# RTI-Dome-eth-ENC.net
KiCad netlist of a schematic drawn in EAGLE
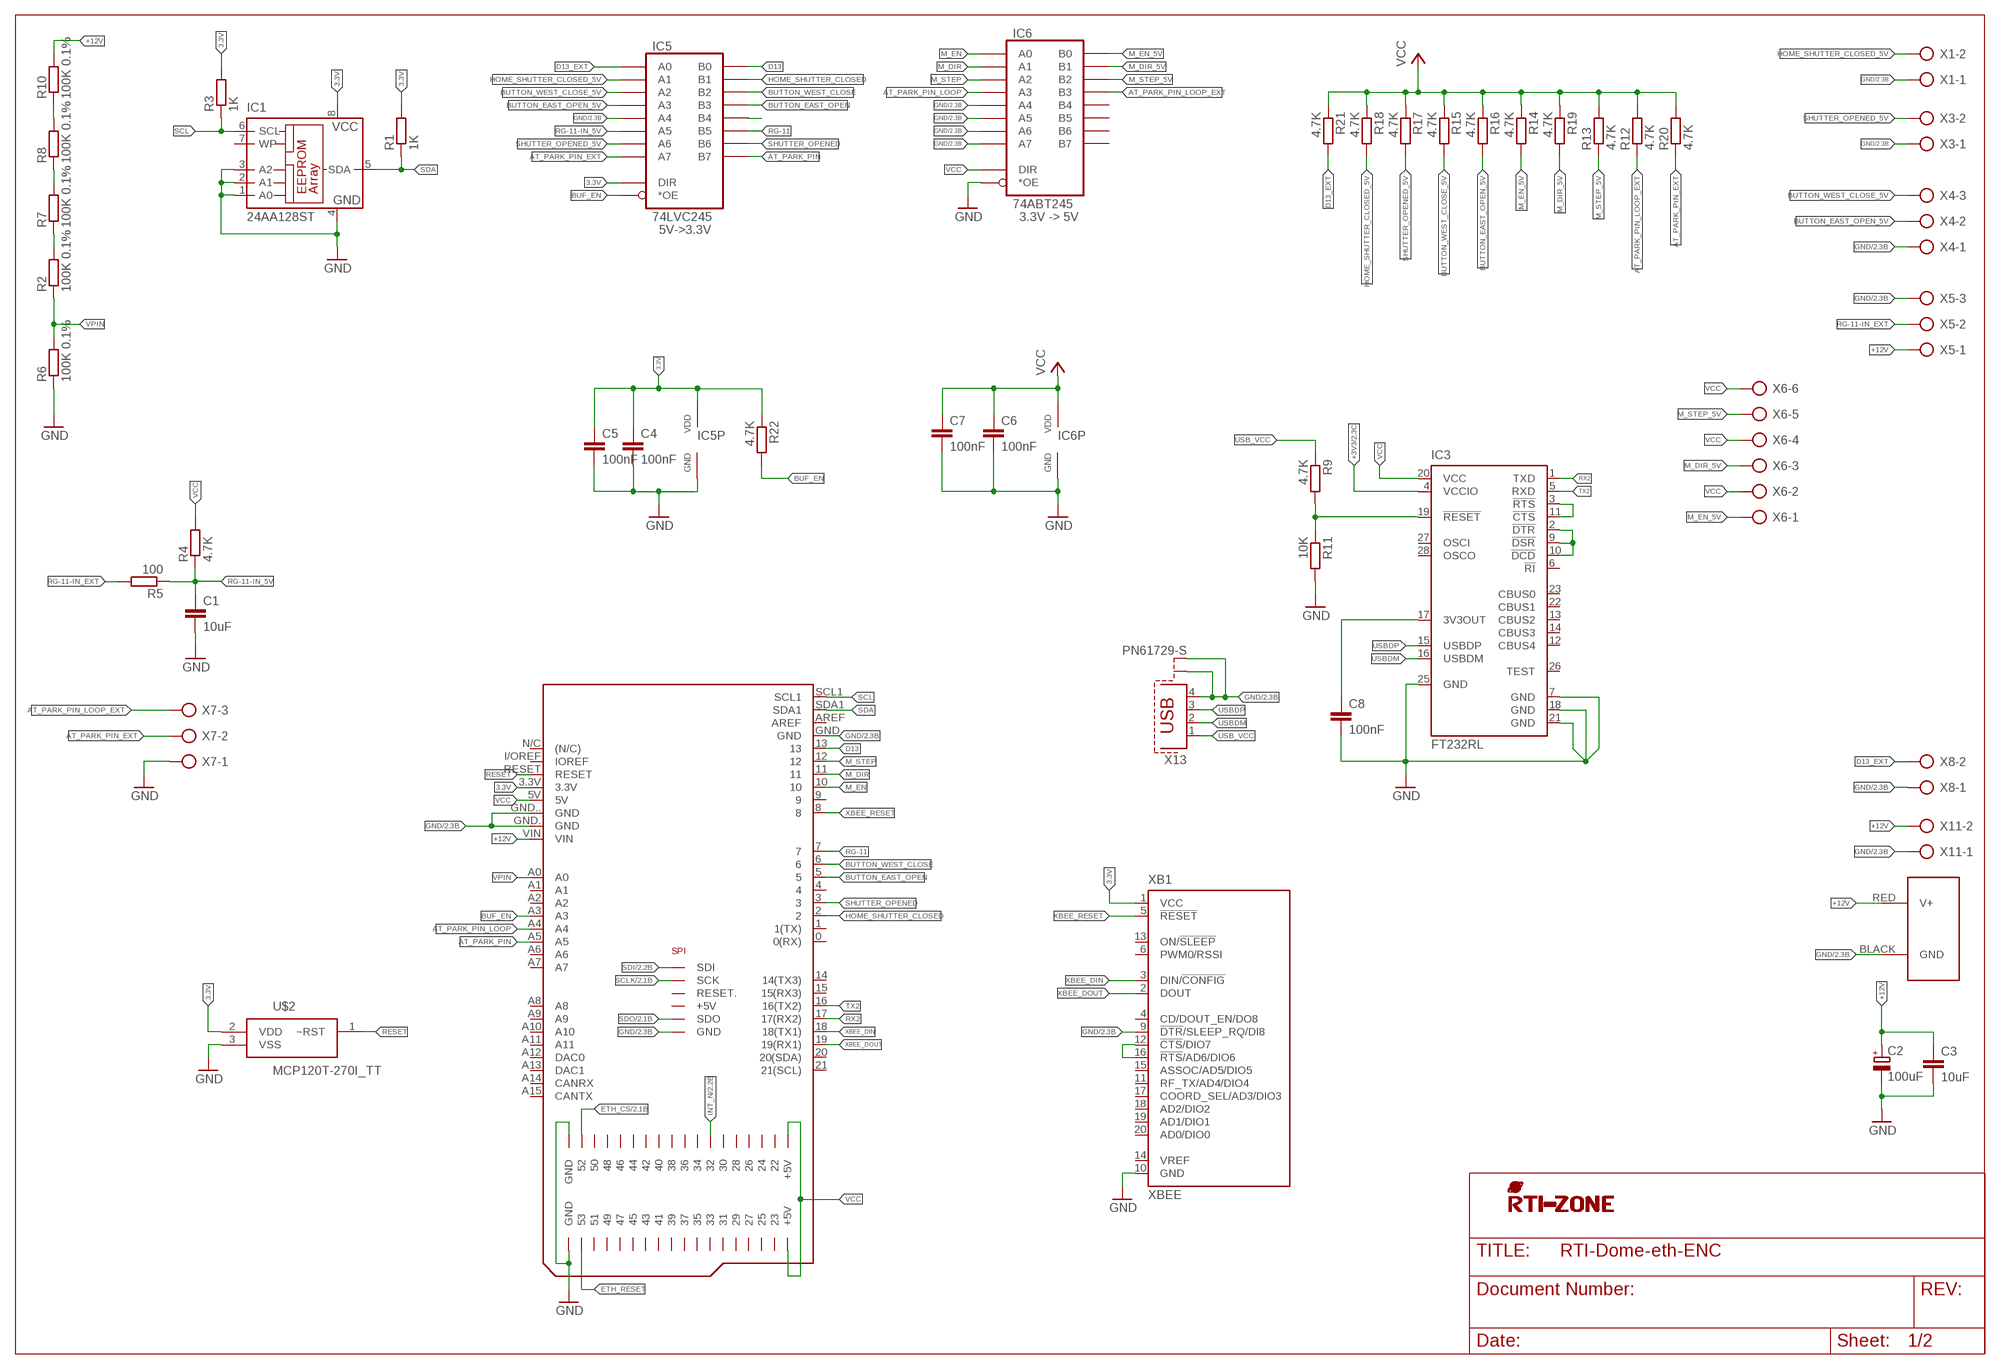
[diagram p0: schematic, sheet 1]
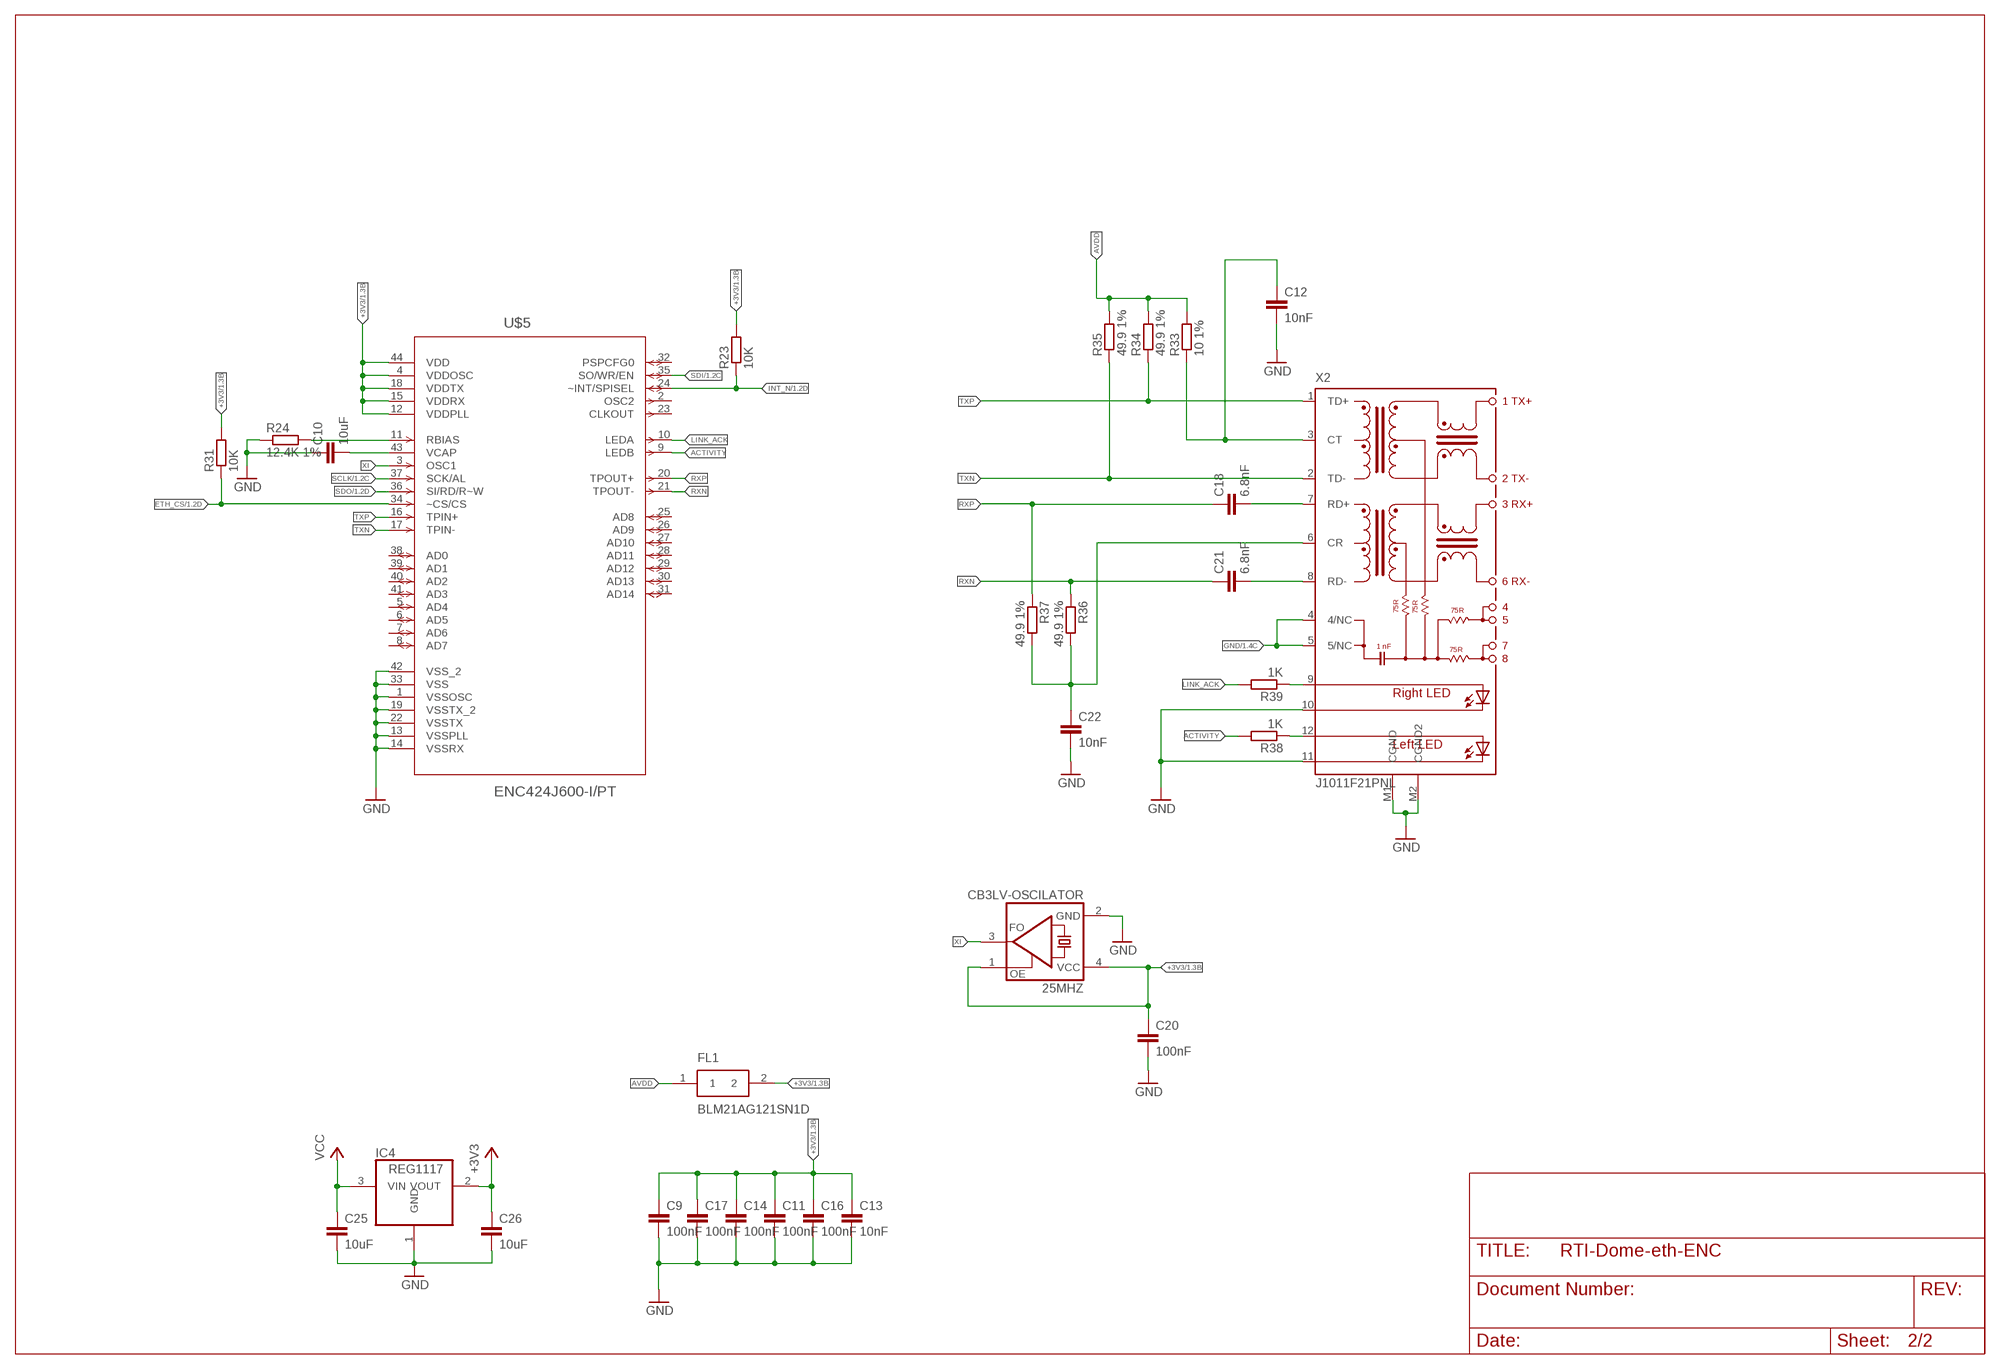
[diagram p1: schematic, sheet 2]

(export (version "E")
  (design (tool "Eeschema 10.0.6"))
  (components
    (comp (ref "25MHZ")
      (value "CB3LV-OSCILATOR")
      (footprint "eagle-import:SMD-7050_4P")
      (fields (field (name "MPN") "O705025MEDH4MI"))
      (libsource (lib "eagle-import") (part "CB3LV-OSCILATOR"))
    )
    (comp (ref "C9")
      (value "100nF")
      (footprint "eagle-import:C0805")
      (libsource (lib "eagle-import") (part "C-EU'0805'"))
    )
    (comp (ref "C10")
      (value "10uF")
      (footprint "eagle-import:C0805")
      (libsource (lib "eagle-import") (part "C-EU'0805'"))
    )
    (comp (ref "C11")
      (value "100nF")
      (footprint "eagle-import:C0805")
      (libsource (lib "eagle-import") (part "C-EU'0805'"))
    )
    (comp (ref "C12")
      (value "10nF")
      (footprint "eagle-import:C0805")
      (libsource (lib "eagle-import") (part "C-EU'0805'"))
    )
    (comp (ref "C13")
      (value "10nF")
      (footprint "eagle-import:C0805")
      (libsource (lib "eagle-import") (part "C-EU'0805'"))
    )
    (comp (ref "C14")
      (value "100nF")
      (footprint "eagle-import:C0805")
      (libsource (lib "eagle-import") (part "C-EU'0805'"))
    )
    (comp (ref "C16")
      (value "100nF")
      (footprint "eagle-import:C0805")
      (libsource (lib "eagle-import") (part "C-EU'0805'"))
    )
    (comp (ref "C17")
      (value "100nF")
      (footprint "eagle-import:C0805")
      (libsource (lib "eagle-import") (part "C-EU'0805'"))
    )
    (comp (ref "C18")
      (value "6.8nF")
      (footprint "eagle-import:C0805")
      (libsource (lib "eagle-import") (part "C-EU'0805'"))
    )
    (comp (ref "C20")
      (value "100nF")
      (footprint "eagle-import:C0805")
      (libsource (lib "eagle-import") (part "C-EU'0805'"))
    )
    (comp (ref "C21")
      (value "6.8nF")
      (footprint "eagle-import:C0805")
      (libsource (lib "eagle-import") (part "C-EU'0805'"))
    )
    (comp (ref "C22")
      (value "10nF")
      (footprint "eagle-import:C0805")
      (libsource (lib "eagle-import") (part "C-EU'0805'"))
    )
    (comp (ref "C25")
      (value "10uF")
      (footprint "eagle-import:C1206")
      (libsource (lib "eagle-import") (part "C-EU'1206'"))
    )
    (comp (ref "C26")
      (value "10uF")
      (footprint "eagle-import:C1206")
      (libsource (lib "eagle-import") (part "C-EU'1206'"))
    )
    (comp (ref "FL1")
      (value "BLM21AG121SN1D")
      (footprint "eagle-import:L0805")
      (libsource (lib "eagle-import") (part "BLM21AG121SN1D"))
    )
    (comp (ref "IC4")
      (value "REG1117")
      (footprint "eagle-import:SOT223")
      (fields (field (name "MPN") "REG1117-3.3/2K5"))
      (libsource (lib "eagle-import") (part "REG1117"))
    )
    (comp (ref "R23")
      (value "10K")
      (footprint "eagle-import:R0805")
      (libsource (lib "eagle-import") (part "R-EU'0805'"))
    )
    (comp (ref "R24")
      (value "12.4K 1%")
      (footprint "eagle-import:R0805")
      (libsource (lib "eagle-import") (part "R-EU'0805'"))
    )
    (comp (ref "R31")
      (value "10K")
      (footprint "eagle-import:R0805")
      (libsource (lib "eagle-import") (part "R-EU'0805'"))
    )
    (comp (ref "R33")
      (value "10 1%")
      (footprint "eagle-import:R0805")
      (libsource (lib "eagle-import") (part "R-EU'0805'"))
    )
    (comp (ref "R34")
      (value "49.9 1%")
      (footprint "eagle-import:R0805")
      (libsource (lib "eagle-import") (part "R-EU'0805'"))
    )
    (comp (ref "R35")
      (value "49.9 1%")
      (footprint "eagle-import:R0805")
      (libsource (lib "eagle-import") (part "R-EU'0805'"))
    )
    (comp (ref "R36")
      (value "49.9 1%")
      (footprint "eagle-import:R0805")
      (libsource (lib "eagle-import") (part "R-EU'0805'"))
    )
    (comp (ref "R37")
      (value "49.9 1%")
      (footprint "eagle-import:R0805")
      (libsource (lib "eagle-import") (part "R-EU'0805'"))
    )
    (comp (ref "R38")
      (value "1K")
      (footprint "eagle-import:R0805")
      (libsource (lib "eagle-import") (part "R-EU'0805'"))
    )
    (comp (ref "R39")
      (value "1K")
      (footprint "eagle-import:R0805")
      (libsource (lib "eagle-import") (part "R-EU'0805'"))
    )
    (comp (ref "U$5")
      (value "ENC424J600-I/PT")
      (footprint "eagle-import:QFP50P1200X1200X120-44N")
      (fields (field (name "MPN") "enc424j600-I/pt") (field (name "MPN_1") "ENC424J600-I/PT"))
      (libsource (lib "eagle-import") (part "ENC424J600-I/PT"))
    )
    (comp (ref "X2")
      (value "J1011F21PNL")
      (footprint "eagle-import:J1")
      (libsource (lib "eagle-import") (part "J1011F21PNL"))
    )
    (comp (ref "C1")
      (value "10uF")
      (footprint "eagle-import:C0805")
      (libsource (lib "eagle-import") (part "C-EU'0805'"))
    )
    (comp (ref "C2")
      (value "100uF")
      (footprint "eagle-import:UD-10X10_NICHICON")
      (libsource (lib "eagle-import") (part "CPOL-EU"))
    )
    (comp (ref "C3")
      (value "10uF")
      (footprint "eagle-import:C0805")
      (libsource (lib "eagle-import") (part "C-EU'0805'"))
    )
    (comp (ref "C4")
      (value "100nF")
      (footprint "eagle-import:C0805")
      (libsource (lib "eagle-import") (part "C-EU'0805'"))
    )
    (comp (ref "C5")
      (value "100nF")
      (footprint "eagle-import:C0805")
      (libsource (lib "eagle-import") (part "C-EU'0805'"))
    )
    (comp (ref "C6")
      (value "100nF")
      (footprint "eagle-import:C0805")
      (libsource (lib "eagle-import") (part "C-EU'0805'"))
    )
    (comp (ref "C7")
      (value "100nF")
      (footprint "eagle-import:C0805")
      (libsource (lib "eagle-import") (part "C-EU'0805'"))
    )
    (comp (ref "C8")
      (value "100nF")
      (footprint "eagle-import:C0805")
      (libsource (lib "eagle-import") (part "C-EU'0805'"))
    )
    (comp (ref "IC1")
      (value "24AA128ST")
      (footprint "eagle-import:TSSOP8")
      (fields (field (name "MF") "MICROCHIP") (field (name "MPN") "24AA128-I/ST"))
      (libsource (lib "eagle-import") (part "24STAA128"))
    )
    (comp (ref "IC3")
      (value "FT232RL")
      (footprint "eagle-import:SSOP28")
      (libsource (lib "eagle-import") (part "FT232RL"))
    )
    (comp (ref "IC5")
      (value "74LVC245")
      (footprint "eagle-import:TSSOP20")
      (fields (field (name "MPN") "74LVC245APW,118"))
      (libsource (lib "eagle-import") (part "74245LVC"))
    )
    (comp (ref "IC6")
      (value "74ABT245")
      (footprint "eagle-import:TSSOP20")
      (fields (field (name "MPN") "SN74ABT245BDWR"))
      (libsource (lib "eagle-import") (part "74245ABT"))
    )
    (comp (ref "J1")
      (value "POWERPOLE_POWER45A")
      (footprint "eagle-import:POWERPOLE_PAIR_45A")
      (libsource (lib "eagle-import") (part "POWERPOLE_POWER45A"))
    )
    (comp (ref "R1")
      (value "1K")
      (footprint "eagle-import:R0805")
      (libsource (lib "eagle-import") (part "R-EU'0805'"))
    )
    (comp (ref "R2")
      (value "100K 0.1%")
      (footprint "eagle-import:R0805")
      (libsource (lib "eagle-import") (part "R-EU'0805'"))
    )
    (comp (ref "R3")
      (value "1K")
      (footprint "eagle-import:R0805")
      (libsource (lib "eagle-import") (part "R-EU'0805'"))
    )
    (comp (ref "R4")
      (value "4.7K")
      (footprint "eagle-import:R0805")
      (libsource (lib "eagle-import") (part "R-EU'0805'"))
    )
    (comp (ref "R5")
      (value "100")
      (footprint "eagle-import:R0805")
      (libsource (lib "eagle-import") (part "R-EU'0805'"))
    )
    (comp (ref "R6")
      (value "100K 0.1%")
      (footprint "eagle-import:R0805")
      (libsource (lib "eagle-import") (part "R-EU'0805'"))
    )
    (comp (ref "R7")
      (value "100K 0.1%")
      (footprint "eagle-import:R0805")
      (libsource (lib "eagle-import") (part "R-EU'0805'"))
    )
    (comp (ref "R8")
      (value "100K 0.1%")
      (footprint "eagle-import:R0805")
      (libsource (lib "eagle-import") (part "R-EU'0805'"))
    )
    (comp (ref "R9")
      (value "4.7K")
      (footprint "eagle-import:R0805")
      (libsource (lib "eagle-import") (part "R-EU'0805'"))
    )
    (comp (ref "R10")
      (value "100K 0.1%")
      (footprint "eagle-import:R0805")
      (libsource (lib "eagle-import") (part "R-EU'0805'"))
    )
    (comp (ref "R11")
      (value "10K")
      (footprint "eagle-import:R0805")
      (libsource (lib "eagle-import") (part "R-EU'0805'"))
    )
    (comp (ref "R12")
      (value "4.7K")
      (footprint "eagle-import:R0805")
      (libsource (lib "eagle-import") (part "R-EU'0805'"))
    )
    (comp (ref "R13")
      (value "4.7K")
      (footprint "eagle-import:R0805")
      (libsource (lib "eagle-import") (part "R-EU'0805'"))
    )
    (comp (ref "R14")
      (value "4.7K")
      (footprint "eagle-import:R0805")
      (libsource (lib "eagle-import") (part "R-EU'0805'"))
    )
    (comp (ref "R15")
      (value "4.7K")
      (footprint "eagle-import:R0805")
      (libsource (lib "eagle-import") (part "R-EU'0805'"))
    )
    (comp (ref "R16")
      (value "4.7K")
      (footprint "eagle-import:R0805")
      (libsource (lib "eagle-import") (part "R-EU'0805'"))
    )
    (comp (ref "R17")
      (value "4.7K")
      (footprint "eagle-import:R0805")
      (libsource (lib "eagle-import") (part "R-EU'0805'"))
    )
    (comp (ref "R18")
      (value "4.7K")
      (footprint "eagle-import:R0805")
      (libsource (lib "eagle-import") (part "R-EU'0805'"))
    )
    (comp (ref "R19")
      (value "4.7K")
      (footprint "eagle-import:R0805")
      (libsource (lib "eagle-import") (part "R-EU'0805'"))
    )
    (comp (ref "R20")
      (value "4.7K")
      (footprint "eagle-import:R0805")
      (libsource (lib "eagle-import") (part "R-EU'0805'"))
    )
    (comp (ref "R21")
      (value "4.7K")
      (footprint "eagle-import:R0805")
      (libsource (lib "eagle-import") (part "R-EU'0805'"))
    )
    (comp (ref "R22")
      (value "4.7K")
      (footprint "eagle-import:R0805")
      (libsource (lib "eagle-import") (part "R-EU'0805'"))
    )
    (comp (ref "U$1")
      (value "ARDUINO_DUE_SHIELD_FULL")
      (footprint "eagle-import:ARDUINO_DUE_SHIELD_FULL")
      (libsource (lib "eagle-import") (part "ARDUINO_DUE_SHIELD_FULL"))
    )
    (comp (ref "U$2")
      (value "MCP120T-270I_TT")
      (footprint "eagle-import:SOT95P237X112-3N")
      (fields
        (field (name "MANUFACTURER_PART_NUMBER") "MCP120T-270I/TT")
        (field (name "MOUSER_PART_NUMBER") "579-MCP120T-270I/TT")
      )
      (libsource (lib "eagle-import") (part "MCP120T-270I_TT"))
    )
    (comp (ref "U$4")
      (value "RTI-LOGO_BIG")
      (footprint "eagle-import:LOGO_BIG")
      (libsource (lib "eagle-import") (part "RTI-LOGO_BIG"))
    )
    (comp (ref "X1")
      (value "AK500/2")
      (footprint "eagle-import:AK500_2")
      (libsource (lib "eagle-import") (part "AK500/2"))
    )
    (comp (ref "X3")
      (value "AK500/2")
      (footprint "eagle-import:AK500_2")
      (libsource (lib "eagle-import") (part "AK500/2"))
    )
    (comp (ref "X4")
      (value "AK500/3")
      (footprint "eagle-import:AK500_3")
      (libsource (lib "eagle-import") (part "AK500/3"))
    )
    (comp (ref "X5")
      (value "AK500/3")
      (footprint "eagle-import:AK500_3")
      (libsource (lib "eagle-import") (part "AK500/3"))
    )
    (comp (ref "X6")
      (value "AK500/6")
      (footprint "eagle-import:AK500_6")
      (libsource (lib "eagle-import") (part "AK500/6"))
    )
    (comp (ref "X7")
      (value "AK500/3")
      (footprint "eagle-import:AK500_3")
      (libsource (lib "eagle-import") (part "AK500/3"))
    )
    (comp (ref "X8")
      (value "AK500/2")
      (footprint "eagle-import:AK500_2")
      (libsource (lib "eagle-import") (part "AK500/2"))
    )
    (comp (ref "X11")
      (value "AK500/2")
      (footprint "eagle-import:AK500_2")
      (libsource (lib "eagle-import") (part "AK500/2"))
    )
    (comp (ref "X13")
      (value "PN61729-S")
      (footprint "eagle-import:PN61729-S")
      (libsource (lib "eagle-import") (part "PN61729-S"))
    )
    (comp (ref "XB1")
      (value "XBEE")
      (footprint "eagle-import:XBEE")
      (fields (field (name "MPN") "XBP24-Z7UIT-004"))
      (libsource (lib "eagle-import") (part "XBEE"))
    )
  )
  (nets
    (net (code "1") (name "+3V3") (class "Default")
      (node (ref "25MHZ") (pin "1") (pinfunction "OE_1") (pintype "input"))
      (node (ref "25MHZ") (pin "4") (pinfunction "VDD_4") (pintype "power_in"))
      (node (ref "C11") (pin "1") (pinfunction "1_1") (pintype "passive"))
      (node (ref "C13") (pin "1") (pinfunction "1_1") (pintype "passive"))
      (node (ref "C14") (pin "1") (pinfunction "1_1") (pintype "passive"))
      (node (ref "C16") (pin "1") (pinfunction "1_1") (pintype "passive"))
      (node (ref "C17") (pin "1") (pinfunction "1_1") (pintype "passive"))
      (node (ref "C20") (pin "1") (pinfunction "1_1") (pintype "passive"))
      (node (ref "C26") (pin "1") (pinfunction "1_1") (pintype "passive"))
      (node (ref "C9") (pin "1") (pinfunction "1_1") (pintype "passive"))
      (node (ref "FL1") (pin "2") (pinfunction "2_2") (pintype "bidirectional"))
      (node (ref "IC3") (pin "4") (pinfunction "VCCIO_4") (pintype "power_in"))
      (node (ref "IC4") (pin "2") (pinfunction "VOUT_2") (pintype "output"))
      (node (ref "R23") (pin "2") (pinfunction "2_2") (pintype "passive"))
      (node (ref "R31") (pin "2") (pinfunction "2_2") (pintype "passive"))
      (node (ref "U$5") (pin "12") (pinfunction "VDDPLL_12") (pintype "power_in"))
      (node (ref "U$5") (pin "15") (pinfunction "VDDRX_15") (pintype "power_in"))
      (node (ref "U$5") (pin "18") (pinfunction "VDDTX_18") (pintype "power_in"))
      (node (ref "U$5") (pin "4") (pinfunction "VDDOSC_4") (pintype "power_in"))
      (node (ref "U$5") (pin "44") (pinfunction "VDD_44") (pintype "power_in"))
    )
    (net (code "2") (name "+5V") (class "Default")
      (node (ref "U$1") (pin "+5V_") (pinfunction "+5V_+5V_") (pintype "power_in"))
    )
    (net (code "3") (name "+12V") (class "Default")
      (node (ref "C2") (pin "+") (pinfunction "+_+") (pintype "passive"))
      (node (ref "C3") (pin "1") (pinfunction "1_1") (pintype "passive"))
      (node (ref "J1") (pin "RED") (pinfunction "V+_RED") (pintype "power_in"))
      (node (ref "R10") (pin "2") (pinfunction "2_2") (pintype "passive"))
      (node (ref "U$1") (pin "VIN") (pinfunction "VIN_VIN") (pintype "power_in"))
      (node (ref "X11") (pin "2") (pinfunction "KL_2") (pintype "passive"))
      (node (ref "X5") (pin "1") (pinfunction "KL_1") (pintype "passive"))
    )
    (net (code "4") (name "3.3V") (class "Default")
      (node (ref "C4") (pin "1") (pinfunction "1_1") (pintype "passive"))
      (node (ref "C5") (pin "1") (pinfunction "1_1") (pintype "passive"))
      (node (ref "IC1") (pin "8") (pinfunction "VCC_8") (pintype "power_in"))
      (node (ref "IC5") (pin "P$1") (pinfunction "DIR_P$1") (pintype "input"))
      (node (ref "IC5") (pin "P$20") (pinfunction "VDD_P$20") (pintype "power_in"))
      (node (ref "R1") (pin "2") (pinfunction "2_2") (pintype "passive"))
      (node (ref "R22") (pin "1") (pinfunction "1_1") (pintype "passive"))
      (node (ref "R3") (pin "2") (pinfunction "2_2") (pintype "passive"))
      (node (ref "U$1") (pin "3.3V") (pinfunction "3.3V_3.3V") (pintype "power_in"))
      (node (ref "U$2") (pin "2") (pinfunction "VDD_2") (pintype "bidirectional"))
      (node (ref "XB1") (pin "1") (pinfunction "VCC_1") (pintype "power_in"))
    )
    (net (code "5") (name "ACTIVITY") (class "Default")
      (node (ref "R38") (pin "2") (pinfunction "2_2") (pintype "passive"))
      (node (ref "U$5") (pin "9") (pinfunction "LEDB_9") (pintype "output"))
    )
    (net (code "6") (name "AT_PARK_PIN") (class "Default")
      (node (ref "IC5") (pin "P$11") (pinfunction "B7_P$11") (pintype "bidirectional"))
      (node (ref "U$1") (pin "A5") (pinfunction "A5_A5") (pintype "bidirectional"))
    )
    (net (code "7") (name "AT_PARK_PIN_EXT") (class "Default")
      (node (ref "IC5") (pin "P$9") (pinfunction "A7_P$9") (pintype "bidirectional"))
      (node (ref "R20") (pin "1") (pinfunction "1_1") (pintype "passive"))
      (node (ref "X7") (pin "2") (pinfunction "KL_2") (pintype "passive"))
    )
    (net (code "8") (name "AT_PARK_PIN_LOOP") (class "Default")
      (node (ref "IC6") (pin "P$5") (pinfunction "A3_P$5") (pintype "bidirectional"))
      (node (ref "U$1") (pin "A4") (pinfunction "A4_A4") (pintype "bidirectional"))
    )
    (net (code "9") (name "AT_PARK_PIN_LOOP_EXT") (class "Default")
      (node (ref "IC6") (pin "P$15") (pinfunction "B3_P$15") (pintype "bidirectional"))
      (node (ref "R12") (pin "1") (pinfunction "1_1") (pintype "passive"))
      (node (ref "X7") (pin "3") (pinfunction "KL_3") (pintype "passive"))
    )
    (net (code "10") (name "AVDD") (class "Default")
      (node (ref "FL1") (pin "1") (pinfunction "1_1") (pintype "bidirectional"))
      (node (ref "R33") (pin "2") (pinfunction "2_2") (pintype "passive"))
      (node (ref "R34") (pin "2") (pinfunction "2_2") (pintype "passive"))
      (node (ref "R35") (pin "2") (pinfunction "2_2") (pintype "passive"))
    )
    (net (code "11") (name "BUF_EN") (class "Default")
      (node (ref "IC5") (pin "P$19") (pinfunction "*OE_P$19") (pintype "input"))
      (node (ref "R22") (pin "2") (pinfunction "2_2") (pintype "passive"))
      (node (ref "U$1") (pin "A3") (pinfunction "A3_A3") (pintype "bidirectional"))
    )
    (net (code "12") (name "BUTTON_EAST_OPEN") (class "Default")
      (node (ref "IC5") (pin "P$15") (pinfunction "B3_P$15") (pintype "bidirectional"))
      (node (ref "U$1") (pin "5") (pinfunction "5_5") (pintype "bidirectional"))
    )
    (net (code "13") (name "BUTTON_EAST_OPEN_5V") (class "Default")
      (node (ref "IC5") (pin "P$5") (pinfunction "A3_P$5") (pintype "bidirectional"))
      (node (ref "R16") (pin "2") (pinfunction "2_2") (pintype "passive"))
      (node (ref "X4") (pin "2") (pinfunction "KL_2") (pintype "passive"))
    )
    (net (code "14") (name "BUTTON_WEST_CLOSE") (class "Default")
      (node (ref "IC5") (pin "P$16") (pinfunction "B2_P$16") (pintype "bidirectional"))
      (node (ref "U$1") (pin "6") (pinfunction "6_6") (pintype "bidirectional"))
    )
    (net (code "15") (name "BUTTON_WEST_CLOSE_5V") (class "Default")
      (node (ref "IC5") (pin "P$4") (pinfunction "A2_P$4") (pintype "bidirectional"))
      (node (ref "R15") (pin "2") (pinfunction "2_2") (pintype "passive"))
      (node (ref "X4") (pin "3") (pinfunction "KL_3") (pintype "passive"))
    )
    (net (code "16") (name "D13") (class "Default")
      (node (ref "IC5") (pin "P$18") (pinfunction "B0_P$18") (pintype "bidirectional"))
      (node (ref "U$1") (pin "13") (pinfunction "13_13") (pintype "bidirectional"))
    )
    (net (code "17") (name "D13_EXT") (class "Default")
      (node (ref "IC5") (pin "P$2") (pinfunction "A0_P$2") (pintype "bidirectional"))
      (node (ref "R21") (pin "2") (pinfunction "2_2") (pintype "passive"))
      (node (ref "X8") (pin "2") (pinfunction "KL_2") (pintype "passive"))
    )
    (net (code "18") (name "ETH_CS") (class "Default")
      (node (ref "R31") (pin "1") (pinfunction "1_1") (pintype "passive"))
      (node (ref "U$1") (pin "52") (pinfunction "52_52") (pintype "bidirectional"))
      (node (ref "U$5") (pin "34") (pinfunction "~{CS/CS}_34") (pintype "input"))
    )
    (net (code "19") (name "ETH_RESET") (class "Default")
      (node (ref "U$1") (pin "53") (pinfunction "53_53") (pintype "bidirectional"))
    )
    (net (code "20") (name "GND") (class "Default")
      (node (ref "25MHZ") (pin "2") (pinfunction "GND_2") (pintype "power_in"))
      (node (ref "C1") (pin "2") (pinfunction "2_2") (pintype "passive"))
      (node (ref "C10") (pin "1") (pinfunction "1_1") (pintype "passive"))
      (node (ref "C11") (pin "2") (pinfunction "2_2") (pintype "passive"))
      (node (ref "C12") (pin "2") (pinfunction "2_2") (pintype "passive"))
      (node (ref "C13") (pin "2") (pinfunction "2_2") (pintype "passive"))
      (node (ref "C14") (pin "2") (pinfunction "2_2") (pintype "passive"))
      (node (ref "C16") (pin "2") (pinfunction "2_2") (pintype "passive"))
      (node (ref "C17") (pin "2") (pinfunction "2_2") (pintype "passive"))
      (node (ref "C2") (pin "-") (pinfunction "-_-") (pintype "passive"))
      (node (ref "C20") (pin "2") (pinfunction "2_2") (pintype "passive"))
      (node (ref "C22") (pin "2") (pinfunction "2_2") (pintype "passive"))
      (node (ref "C25") (pin "2") (pinfunction "2_2") (pintype "passive"))
      (node (ref "C26") (pin "2") (pinfunction "2_2") (pintype "passive"))
      (node (ref "C3") (pin "2") (pinfunction "2_2") (pintype "passive"))
      (node (ref "C4") (pin "2") (pinfunction "2_2") (pintype "passive"))
      (node (ref "C5") (pin "2") (pinfunction "2_2") (pintype "passive"))
      (node (ref "C6") (pin "2") (pinfunction "2_2") (pintype "passive"))
      (node (ref "C7") (pin "2") (pinfunction "2_2") (pintype "passive"))
      (node (ref "C8") (pin "2") (pinfunction "2_2") (pintype "passive"))
      (node (ref "C9") (pin "2") (pinfunction "2_2") (pintype "passive"))
      (node (ref "IC1") (pin "1") (pinfunction "A0_1") (pintype "input"))
      (node (ref "IC1") (pin "2") (pinfunction "A1_2") (pintype "input"))
      (node (ref "IC1") (pin "3") (pinfunction "A2_3") (pintype "input"))
      (node (ref "IC1") (pin "4") (pinfunction "GND_4") (pintype "power_in"))
      (node (ref "IC3") (pin "18") (pinfunction "GND_18") (pintype "power_in"))
      (node (ref "IC3") (pin "21") (pinfunction "GND_21") (pintype "power_in"))
      (node (ref "IC3") (pin "25") (pinfunction "GND_25") (pintype "power_in"))
      (node (ref "IC3") (pin "7") (pinfunction "GND_7") (pintype "power_in"))
      (node (ref "IC4") (pin "1") (pinfunction "GND_1") (pintype "power_in"))
      (node (ref "IC5") (pin "P$10") (pinfunction "GND_P$10") (pintype "power_in"))
      (node (ref "IC5") (pin "P$6") (pinfunction "A4_P$6") (pintype "bidirectional"))
      (node (ref "IC6") (pin "P$10") (pinfunction "GND_P$10") (pintype "power_in"))
      (node (ref "IC6") (pin "P$19") (pinfunction "*OE_P$19") (pintype "input"))
      (node (ref "IC6") (pin "P$6") (pinfunction "A4_P$6") (pintype "bidirectional"))
      (node (ref "IC6") (pin "P$7") (pinfunction "A5_P$7") (pintype "bidirectional"))
      (node (ref "IC6") (pin "P$8") (pinfunction "A6_P$8") (pintype "bidirectional"))
      (node (ref "IC6") (pin "P$9") (pinfunction "A7_P$9") (pintype "bidirectional"))
      (node (ref "J1") (pin "BLACK") (pinfunction "GND_BLACK") (pintype "power_in"))
      (node (ref "R11") (pin "2") (pinfunction "2_2") (pintype "passive"))
      (node (ref "R24") (pin "1") (pinfunction "1_1") (pintype "passive"))
      (node (ref "R6") (pin "1") (pinfunction "1_1") (pintype "passive"))
      (node (ref "U$1") (pin "GND") (pinfunction "GND_GND") (pintype "power_in"))
      (node (ref "U$1") (pin "GND.") (pinfunction "GND_GND.") (pintype "power_in"))
      (node (ref "U$1") (pin "GND..") (pinfunction "GND_GND..") (pintype "power_in"))
      (node (ref "U$1") (pin "GND...") (pinfunction "GND_GND...") (pintype "power_in"))
      (node (ref "U$1") (pin "GND....") (pinfunction "GND_GND....") (pintype "power_in"))
      (node (ref "U$1") (pin "GND__") (pinfunction "GND_GND__") (pintype "power_in"))
      (node (ref "U$2") (pin "3") (pinfunction "VSS_3") (pintype "bidirectional"))
      (node (ref "U$5") (pin "1") (pinfunction "VSSOSC_1") (pintype "power_in"))
      (node (ref "U$5") (pin "13") (pinfunction "VSSPLL_13") (pintype "power_in"))
      (node (ref "U$5") (pin "14") (pinfunction "VSSRX_14") (pintype "power_in"))
      (node (ref "U$5") (pin "19") (pinfunction "VSSTX_2_19") (pintype "power_in"))
      (node (ref "U$5") (pin "22") (pinfunction "VSSTX_22") (pintype "power_in"))
      (node (ref "U$5") (pin "33") (pinfunction "VSS_33") (pintype "power_in"))
      (node (ref "U$5") (pin "42") (pinfunction "VSS_2_42") (pintype "power_in"))
      (node (ref "X1") (pin "1") (pinfunction "KL_1") (pintype "passive"))
      (node (ref "X11") (pin "1") (pinfunction "KL_1") (pintype "passive"))
      (node (ref "X13") (pin "4") (pinfunction "4_4") (pintype "passive"))
      (node (ref "X13") (pin "S1") (pinfunction "S1_S1") (pintype "passive"))
      (node (ref "X13") (pin "S2") (pinfunction "S2_S2") (pintype "passive"))
      (node (ref "X2") (pin "10") (pinfunction "C-R_10") (pintype "passive"))
      (node (ref "X2") (pin "11") (pinfunction "C-L_11") (pintype "passive"))
      (node (ref "X2") (pin "4") (pinfunction "4/NC_4") (pintype "input"))
      (node (ref "X2") (pin "5") (pinfunction "5/NC_5") (pintype "input"))
      (node (ref "X2") (pin "M1") (pinfunction "CGND_M1") (pintype "bidirectional"))
      (node (ref "X2") (pin "M2") (pinfunction "CGND2_M2") (pintype "bidirectional"))
      (node (ref "X3") (pin "1") (pinfunction "KL_1") (pintype "passive"))
      (node (ref "X4") (pin "1") (pinfunction "KL_1") (pintype "passive"))
      (node (ref "X5") (pin "3") (pinfunction "KL_3") (pintype "passive"))
      (node (ref "X7") (pin "1") (pinfunction "KL_1") (pintype "passive"))
      (node (ref "X8") (pin "1") (pinfunction "KL_1") (pintype "passive"))
      (node (ref "XB1") (pin "10") (pinfunction "GND_10") (pintype "power_in"))
      (node (ref "XB1") (pin "9") (pinfunction "~{DTR}/SLEEP_RQ/DI8_9") (pintype "bidirectional"))
    )
    (net (code "21") (name "HOME_SHUTTER_CLOSED") (class "Default")
      (node (ref "IC5") (pin "P$17") (pinfunction "B1_P$17") (pintype "bidirectional"))
      (node (ref "U$1") (pin "2") (pinfunction "2_2") (pintype "bidirectional"))
    )
    (net (code "22") (name "HOME_SHUTTER_CLOSED_5V") (class "Default")
      (node (ref "IC5") (pin "P$3") (pinfunction "A1_P$3") (pintype "bidirectional"))
      (node (ref "R18") (pin "2") (pinfunction "2_2") (pintype "passive"))
      (node (ref "X1") (pin "2") (pinfunction "KL_2") (pintype "passive"))
    )
    (net (code "23") (name "INT_N") (class "Default")
      (node (ref "R23") (pin "1") (pinfunction "1_1") (pintype "passive"))
      (node (ref "U$1") (pin "32") (pinfunction "32_32") (pintype "bidirectional"))
      (node (ref "U$5") (pin "24") (pinfunction "~{INT/SPISEL}_24") (pintype "bidirectional"))
    )
    (net (code "24") (name "LINK_ACK") (class "Default")
      (node (ref "R39") (pin "2") (pinfunction "2_2") (pintype "passive"))
      (node (ref "U$5") (pin "10") (pinfunction "LEDA_10") (pintype "output"))
    )
    (net (code "25") (name "M_DIR") (class "Default")
      (node (ref "IC6") (pin "P$3") (pinfunction "A1_P$3") (pintype "bidirectional"))
      (node (ref "U$1") (pin "11") (pinfunction "11_11") (pintype "bidirectional"))
    )
    (net (code "26") (name "M_DIR_5V") (class "Default")
      (node (ref "IC6") (pin "P$17") (pinfunction "B1_P$17") (pintype "bidirectional"))
      (node (ref "R19") (pin "2") (pinfunction "2_2") (pintype "passive"))
      (node (ref "X6") (pin "3") (pinfunction "KL_3") (pintype "passive"))
    )
    (net (code "27") (name "M_EN") (class "Default")
      (node (ref "IC6") (pin "P$2") (pinfunction "A0_P$2") (pintype "bidirectional"))
      (node (ref "U$1") (pin "10") (pinfunction "10_10") (pintype "bidirectional"))
    )
    (net (code "28") (name "M_EN_5V") (class "Default")
      (node (ref "IC6") (pin "P$18") (pinfunction "B0_P$18") (pintype "bidirectional"))
      (node (ref "R14") (pin "2") (pinfunction "2_2") (pintype "passive"))
      (node (ref "X6") (pin "1") (pinfunction "KL_1") (pintype "passive"))
    )
    (net (code "29") (name "M_STEP") (class "Default")
      (node (ref "IC6") (pin "P$4") (pinfunction "A2_P$4") (pintype "bidirectional"))
      (node (ref "U$1") (pin "12") (pinfunction "12_12") (pintype "bidirectional"))
    )
    (net (code "30") (name "M_STEP_5V") (class "Default")
      (node (ref "IC6") (pin "P$16") (pinfunction "B2_P$16") (pintype "bidirectional"))
      (node (ref "R13") (pin "1") (pinfunction "1_1") (pintype "passive"))
      (node (ref "X6") (pin "5") (pinfunction "KL_5") (pintype "passive"))
    )
    (net (code "31") (name "Net-(IC3-3V3OUT)") (class "Default")
      (node (ref "C8") (pin "1") (pinfunction "1_1") (pintype "passive"))
      (node (ref "IC3") (pin "17") (pinfunction "3V3OUT_17") (pintype "output"))
    )
    (net (code "32") (name "Net-(IC3-~{CTS})") (class "Default")
      (node (ref "IC3") (pin "11") (pinfunction "~{CTS}_11") (pintype "input"))
      (node (ref "IC3") (pin "3") (pinfunction "~{RTS}_3") (pintype "output"))
    )
    (net (code "33") (name "Net-(IC3-~{DCD})") (class "Default")
      (node (ref "IC3") (pin "10") (pinfunction "~{DCD}_10") (pintype "input"))
      (node (ref "IC3") (pin "2") (pinfunction "~{DTR}_2") (pintype "output"))
      (node (ref "IC3") (pin "9") (pinfunction "~{DSR}_9") (pintype "input"))
    )
    (net (code "34") (name "Net-(IC3-~{RESET})") (class "Default")
      (node (ref "IC3") (pin "19") (pinfunction "~{RESET}_19") (pintype "input"))
      (node (ref "R11") (pin "1") (pinfunction "1_1") (pintype "passive"))
      (node (ref "R9") (pin "2") (pinfunction "2_2") (pintype "passive"))
    )
    (net (code "35") (name "Net-(R2-Pad2)") (class "Default")
      (node (ref "R2") (pin "2") (pinfunction "2_2") (pintype "passive"))
      (node (ref "R7") (pin "1") (pinfunction "1_1") (pintype "passive"))
    )
    (net (code "36") (name "Net-(R7-Pad2)") (class "Default")
      (node (ref "R7") (pin "2") (pinfunction "2_2") (pintype "passive"))
      (node (ref "R8") (pin "1") (pinfunction "1_1") (pintype "passive"))
    )
    (net (code "37") (name "Net-(R10-Pad1)") (class "Default")
      (node (ref "R10") (pin "1") (pinfunction "1_1") (pintype "passive"))
      (node (ref "R8") (pin "2") (pinfunction "2_2") (pintype "passive"))
    )
    (net (code "38") (name "Net-(U$5-RBIAS)") (class "Default")
      (node (ref "R24") (pin "2") (pinfunction "2_2") (pintype "passive"))
      (node (ref "U$5") (pin "11") (pinfunction "RBIAS_11") (pintype "input"))
    )
    (net (code "39") (name "Net-(U$5-VCAP)") (class "Default")
      (node (ref "C10") (pin "2") (pinfunction "2_2") (pintype "passive"))
      (node (ref "U$5") (pin "43") (pinfunction "VCAP_43") (pintype "power_in"))
    )
    (net (code "40") (name "Net-(X2-A-R)") (class "Default")
      (node (ref "R39") (pin "1") (pinfunction "1_1") (pintype "passive"))
      (node (ref "X2") (pin "9") (pinfunction "A-R_9") (pintype "passive"))
    )
    (net (code "41") (name "Net-(X2-AL)") (class "Default")
      (node (ref "R38") (pin "1") (pinfunction "1_1") (pintype "passive"))
      (node (ref "X2") (pin "12") (pinfunction "AL_12") (pintype "passive"))
    )
    (net (code "42") (name "Net-(X2-CR)") (class "Default")
      (node (ref "C22") (pin "1") (pinfunction "1_1") (pintype "passive"))
      (node (ref "R36") (pin "2") (pinfunction "2_2") (pintype "passive"))
      (node (ref "R37") (pin "2") (pinfunction "2_2") (pintype "passive"))
      (node (ref "X2") (pin "6") (pinfunction "CR_6") (pintype "input"))
    )
    (net (code "43") (name "Net-(X2-CT)") (class "Default")
      (node (ref "C12") (pin "1") (pinfunction "1_1") (pintype "passive"))
      (node (ref "R33") (pin "1") (pinfunction "1_1") (pintype "passive"))
      (node (ref "X2") (pin "3") (pinfunction "CT_3") (pintype "input"))
    )
    (net (code "44") (name "Net-(X2-RD+)") (class "Default")
      (node (ref "C18") (pin "2") (pinfunction "2_2") (pintype "passive"))
      (node (ref "X2") (pin "7") (pinfunction "RD+_7") (pintype "input"))
    )
    (net (code "45") (name "Net-(X2-RD-)") (class "Default")
      (node (ref "C21") (pin "2") (pinfunction "2_2") (pintype "passive"))
      (node (ref "X2") (pin "8") (pinfunction "RD-_8") (pintype "input"))
    )
    (net (code "46") (name "Net-(XB1-~{CTS}{slash}DIO7)") (class "Default")
      (node (ref "XB1") (pin "12") (pinfunction "~{CTS}/DIO7_12") (pintype "bidirectional"))
      (node (ref "XB1") (pin "16") (pinfunction "~{RTS}/AD6/DIO6_16") (pintype "bidirectional"))
    )
    (net (code "47") (name "RESET") (class "Default")
      (node (ref "U$1") (pin "RESET") (pinfunction "RESET_RESET") (pintype "bidirectional"))
      (node (ref "U$2") (pin "1") (pinfunction "~{RST}_1") (pintype "bidirectional"))
    )
    (net (code "48") (name "RG-11") (class "Default")
      (node (ref "IC5") (pin "P$13") (pinfunction "B5_P$13") (pintype "bidirectional"))
      (node (ref "U$1") (pin "7") (pinfunction "7_7") (pintype "bidirectional"))
    )
    (net (code "49") (name "RG-11-IN_5V") (class "Default")
      (node (ref "C1") (pin "1") (pinfunction "1_1") (pintype "passive"))
      (node (ref "IC5") (pin "P$7") (pinfunction "A5_P$7") (pintype "bidirectional"))
      (node (ref "R4") (pin "1") (pinfunction "1_1") (pintype "passive"))
      (node (ref "R5") (pin "1") (pinfunction "1_1") (pintype "passive"))
    )
    (net (code "50") (name "RG-11-IN_EXT") (class "Default")
      (node (ref "R5") (pin "2") (pinfunction "2_2") (pintype "passive"))
      (node (ref "X5") (pin "2") (pinfunction "KL_2") (pintype "passive"))
    )
    (net (code "51") (name "RX2") (class "Default")
      (node (ref "IC3") (pin "1") (pinfunction "TXD_1") (pintype "output"))
      (node (ref "U$1") (pin "17") (pinfunction "17(RX2)_17") (pintype "bidirectional"))
    )
    (net (code "52") (name "RXN") (class "Default")
      (node (ref "C21") (pin "1") (pinfunction "1_1") (pintype "passive"))
      (node (ref "R36") (pin "1") (pinfunction "1_1") (pintype "passive"))
      (node (ref "U$5") (pin "21") (pinfunction "TPOUT-_21") (pintype "output"))
    )
    (net (code "53") (name "RXP") (class "Default")
      (node (ref "C18") (pin "1") (pinfunction "1_1") (pintype "passive"))
      (node (ref "R37") (pin "1") (pinfunction "1_1") (pintype "passive"))
      (node (ref "U$5") (pin "20") (pinfunction "TPOUT+_20") (pintype "output"))
    )
    (net (code "54") (name "SCL") (class "Default")
      (node (ref "IC1") (pin "6") (pinfunction "SCL_6") (pintype "input"))
      (node (ref "R3") (pin "1") (pinfunction "1_1") (pintype "passive"))
      (node (ref "U$1") (pin "SCL1") (pinfunction "SCL1_SCL1") (pintype "bidirectional"))
    )
    (net (code "55") (name "SCLK") (class "Default")
      (node (ref "U$1") (pin "SCK") (pinfunction "SCK_SCK") (pintype "bidirectional"))
      (node (ref "U$5") (pin "37") (pinfunction "SCK/AL_37") (pintype "input"))
    )
    (net (code "56") (name "SDA") (class "Default")
      (node (ref "IC1") (pin "5") (pinfunction "SDA_5") (pintype "bidirectional"))
      (node (ref "R1") (pin "1") (pinfunction "1_1") (pintype "passive"))
      (node (ref "U$1") (pin "SDA1") (pinfunction "SDA1_SDA1") (pintype "bidirectional"))
    )
    (net (code "57") (name "SDI") (class "Default")
      (node (ref "U$1") (pin "MISO") (pinfunction "SDI_MISO") (pintype "bidirectional"))
      (node (ref "U$5") (pin "35") (pinfunction "SO/WR/EN_35") (pintype "bidirectional"))
    )
    (net (code "58") (name "SDO") (class "Default")
      (node (ref "U$1") (pin "MOSI") (pinfunction "SDO_MOSI") (pintype "bidirectional"))
      (node (ref "U$5") (pin "36") (pinfunction "SI/RD/R~{W}_36") (pintype "input"))
    )
    (net (code "59") (name "SHUTTER_OPENED") (class "Default")
      (node (ref "IC5") (pin "P$12") (pinfunction "B6_P$12") (pintype "bidirectional"))
      (node (ref "U$1") (pin "3") (pinfunction "3_3") (pintype "bidirectional"))
    )
    (net (code "60") (name "SHUTTER_OPENED_5V") (class "Default")
      (node (ref "IC5") (pin "P$8") (pinfunction "A6_P$8") (pintype "bidirectional"))
      (node (ref "R17") (pin "2") (pinfunction "2_2") (pintype "passive"))
      (node (ref "X3") (pin "2") (pinfunction "KL_2") (pintype "passive"))
    )
    (net (code "61") (name "TX2") (class "Default")
      (node (ref "IC3") (pin "5") (pinfunction "RXD_5") (pintype "input"))
      (node (ref "U$1") (pin "16") (pinfunction "16(TX2)_16") (pintype "bidirectional"))
    )
    (net (code "62") (name "TXN") (class "Default")
      (node (ref "R35") (pin "1") (pinfunction "1_1") (pintype "passive"))
      (node (ref "U$5") (pin "17") (pinfunction "TPIN-_17") (pintype "input"))
      (node (ref "X2") (pin "2") (pinfunction "TD-_2") (pintype "input"))
    )
    (net (code "63") (name "TXP") (class "Default")
      (node (ref "R34") (pin "1") (pinfunction "1_1") (pintype "passive"))
      (node (ref "U$5") (pin "16") (pinfunction "TPIN+_16") (pintype "input"))
      (node (ref "X2") (pin "1") (pinfunction "TD+_1") (pintype "input"))
    )
    (net (code "64") (name "USBDM") (class "Default")
      (node (ref "IC3") (pin "16") (pinfunction "USBDM_16") (pintype "bidirectional"))
      (node (ref "X13") (pin "2") (pinfunction "2_2") (pintype "passive"))
    )
    (net (code "65") (name "USBDP") (class "Default")
      (node (ref "IC3") (pin "15") (pinfunction "USBDP_15") (pintype "bidirectional"))
      (node (ref "X13") (pin "3") (pinfunction "3_3") (pintype "passive"))
    )
    (net (code "66") (name "USB_VCC") (class "Default")
      (node (ref "R9") (pin "1") (pinfunction "1_1") (pintype "passive"))
      (node (ref "X13") (pin "1") (pinfunction "1_1") (pintype "passive"))
    )
    (net (code "67") (name "VCC") (class "Default")
      (node (ref "C25") (pin "1") (pinfunction "1_1") (pintype "passive"))
      (node (ref "C6") (pin "1") (pinfunction "1_1") (pintype "passive"))
      (node (ref "C7") (pin "1") (pinfunction "1_1") (pintype "passive"))
      (node (ref "IC3") (pin "20") (pinfunction "VCC_20") (pintype "power_in"))
      (node (ref "IC4") (pin "3") (pinfunction "VIN_3") (pintype "input"))
      (node (ref "IC6") (pin "P$1") (pinfunction "DIR_P$1") (pintype "input"))
      (node (ref "IC6") (pin "P$20") (pinfunction "VDD_P$20") (pintype "power_in"))
      (node (ref "R12") (pin "2") (pinfunction "2_2") (pintype "passive"))
      (node (ref "R13") (pin "2") (pinfunction "2_2") (pintype "passive"))
      (node (ref "R14") (pin "1") (pinfunction "1_1") (pintype "passive"))
      (node (ref "R15") (pin "1") (pinfunction "1_1") (pintype "passive"))
      (node (ref "R16") (pin "1") (pinfunction "1_1") (pintype "passive"))
      (node (ref "R17") (pin "1") (pinfunction "1_1") (pintype "passive"))
      (node (ref "R18") (pin "1") (pinfunction "1_1") (pintype "passive"))
      (node (ref "R19") (pin "1") (pinfunction "1_1") (pintype "passive"))
      (node (ref "R20") (pin "2") (pinfunction "2_2") (pintype "passive"))
      (node (ref "R21") (pin "1") (pinfunction "1_1") (pintype "passive"))
      (node (ref "R4") (pin "2") (pinfunction "2_2") (pintype "passive"))
      (node (ref "U$1") (pin "5V") (pinfunction "5V_5V") (pintype "power_in"))
      (node (ref "U$1") (pin "5V.") (pinfunction "+5V_5V.") (pintype "power_in"))
      (node (ref "U$1") (pin "5V..") (pinfunction "+5V_5V..") (pintype "power_in"))
      (node (ref "X6") (pin "2") (pinfunction "KL_2") (pintype "passive"))
      (node (ref "X6") (pin "4") (pinfunction "KL_4") (pintype "passive"))
      (node (ref "X6") (pin "6") (pinfunction "KL_6") (pintype "passive"))
    )
    (net (code "68") (name "VPIN") (class "Default")
      (node (ref "R2") (pin "1") (pinfunction "1_1") (pintype "passive"))
      (node (ref "R6") (pin "2") (pinfunction "2_2") (pintype "passive"))
      (node (ref "U$1") (pin "A0") (pinfunction "A0_A0") (pintype "bidirectional"))
    )
    (net (code "69") (name "XBEE_DIN") (class "Default")
      (node (ref "U$1") (pin "18") (pinfunction "18(TX1)_18") (pintype "bidirectional"))
      (node (ref "XB1") (pin "3") (pinfunction "DIN/~{CONFIG}_3") (pintype "input"))
    )
    (net (code "70") (name "XBEE_DOUT") (class "Default")
      (node (ref "U$1") (pin "19") (pinfunction "19(RX1)_19") (pintype "bidirectional"))
      (node (ref "XB1") (pin "2") (pinfunction "DOUT_2") (pintype "output"))
    )
    (net (code "71") (name "XBEE_RESET") (class "Default")
      (node (ref "U$1") (pin "8") (pinfunction "8_8") (pintype "bidirectional"))
      (node (ref "XB1") (pin "5") (pinfunction "~{RESET}_5") (pintype "input"))
    )
    (net (code "72") (name "XI") (class "Default")
      (node (ref "25MHZ") (pin "3") (pinfunction "FO_3") (pintype "output"))
      (node (ref "U$5") (pin "3") (pinfunction "OSC1_3") (pintype "input"))
    )
    (net (code "73") (name "unconnected-(IC1-WP-Pad7)") (class "Default")
      (node (ref "IC1") (pin "7") (pinfunction "WP_7") (pintype "input"))
    )
    (net (code "74") (name "unconnected-(IC3-CBUS0-Pad23)") (class "Default")
      (node (ref "IC3") (pin "23") (pinfunction "CBUS0_23") (pintype "bidirectional"))
    )
    (net (code "75") (name "unconnected-(IC3-CBUS1-Pad22)") (class "Default")
      (node (ref "IC3") (pin "22") (pinfunction "CBUS1_22") (pintype "bidirectional"))
    )
    (net (code "76") (name "unconnected-(IC3-CBUS2-Pad13)") (class "Default")
      (node (ref "IC3") (pin "13") (pinfunction "CBUS2_13") (pintype "bidirectional"))
    )
    (net (code "77") (name "unconnected-(IC3-CBUS3-Pad14)") (class "Default")
      (node (ref "IC3") (pin "14") (pinfunction "CBUS3_14") (pintype "bidirectional"))
    )
    (net (code "78") (name "unconnected-(IC3-CBUS4-Pad12)") (class "Default")
      (node (ref "IC3") (pin "12") (pinfunction "CBUS4_12") (pintype "bidirectional"))
    )
    (net (code "79") (name "unconnected-(IC3-OSCI-Pad27)") (class "Default")
      (node (ref "IC3") (pin "27") (pinfunction "OSCI_27") (pintype "input"))
    )
    (net (code "80") (name "unconnected-(IC3-OSCO-Pad28)") (class "Default")
      (node (ref "IC3") (pin "28") (pinfunction "OSCO_28") (pintype "output"))
    )
    (net (code "81") (name "unconnected-(IC3-TEST-Pad26)") (class "Default")
      (node (ref "IC3") (pin "26") (pinfunction "TEST_26") (pintype "input"))
    )
    (net (code "82") (name "unconnected-(IC3-~{RI}-Pad6)") (class "Default")
      (node (ref "IC3") (pin "6") (pinfunction "~{RI}_6") (pintype "input"))
    )
    (net (code "83") (name "unconnected-(IC5A-B4-PadP$14)") (class "Default")
      (node (ref "IC5") (pin "P$14") (pinfunction "B4_P$14") (pintype "bidirectional"))
    )
    (net (code "84") (name "unconnected-(IC6A-B4-PadP$14)") (class "Default")
      (node (ref "IC6") (pin "P$14") (pinfunction "B4_P$14") (pintype "bidirectional"))
    )
    (net (code "85") (name "unconnected-(IC6A-B5-PadP$13)") (class "Default")
      (node (ref "IC6") (pin "P$13") (pinfunction "B5_P$13") (pintype "bidirectional"))
    )
    (net (code "86") (name "unconnected-(IC6A-B6-PadP$12)") (class "Default")
      (node (ref "IC6") (pin "P$12") (pinfunction "B6_P$12") (pintype "bidirectional"))
    )
    (net (code "87") (name "unconnected-(IC6A-B7-PadP$11)") (class "Default")
      (node (ref "IC6") (pin "P$11") (pinfunction "B7_P$11") (pintype "bidirectional"))
    )
    (net (code "88") (name "unconnected-(U$1-(N{slash}C)-PadN{slash}C)") (class "Default")
      (node (ref "U$1") (pin "N/C") (pinfunction "(N/C)_N/C") (pintype "no_connect"))
    )
    (net (code "89") (name "unconnected-(U$1-0(RX)-Pad0)") (class "Default")
      (node (ref "U$1") (pin "0") (pinfunction "0(RX)_0") (pintype "bidirectional"))
    )
    (net (code "90") (name "unconnected-(U$1-1(TX)-Pad1)") (class "Default")
      (node (ref "U$1") (pin "1") (pinfunction "1(TX)_1") (pintype "bidirectional"))
    )
    (net (code "91") (name "unconnected-(U$1-14(TX3)-Pad14)") (class "Default")
      (node (ref "U$1") (pin "14") (pinfunction "14(TX3)_14") (pintype "bidirectional"))
    )
    (net (code "92") (name "unconnected-(U$1-15(RX3)-Pad15)") (class "Default")
      (node (ref "U$1") (pin "15") (pinfunction "15(RX3)_15") (pintype "bidirectional"))
    )
    (net (code "93") (name "unconnected-(U$1-20(SDA)-Pad20)") (class "Default")
      (node (ref "U$1") (pin "20") (pinfunction "20(SDA)_20") (pintype "bidirectional"))
    )
    (net (code "94") (name "unconnected-(U$1-21(SCL)-Pad21)") (class "Default")
      (node (ref "U$1") (pin "21") (pinfunction "21(SCL)_21") (pintype "bidirectional"))
    )
    (net (code "95") (name "unconnected-(U$1-CANRX-PadA14)") (class "Default")
      (node (ref "U$1") (pin "A14") (pinfunction "CANRX_A14") (pintype "bidirectional"))
    )
    (net (code "96") (name "unconnected-(U$1-CANTX-PadA15)") (class "Default")
      (node (ref "U$1") (pin "A15") (pinfunction "CANTX_A15") (pintype "bidirectional"))
    )
    (net (code "97") (name "unconnected-(U$1-DAC0-PadA12)") (class "Default")
      (node (ref "U$1") (pin "A12") (pinfunction "DAC0_A12") (pintype "bidirectional"))
    )
    (net (code "98") (name "unconnected-(U$1-DAC1-PadA13)") (class "Default")
      (node (ref "U$1") (pin "A13") (pinfunction "DAC1_A13") (pintype "bidirectional"))
    )
    (net (code "99") (name "unconnected-(U$1-IOREF-PadI{slash}OREF)") (class "Default")
      (node (ref "U$1") (pin "I/OREF") (pinfunction "IOREF_I/OREF") (pintype "bidirectional"))
    )
    (net (code "100") (name "unconnected-(U$1-Pad4)") (class "Default")
      (node (ref "U$1") (pin "4") (pinfunction "4_4") (pintype "bidirectional"))
    )
    (net (code "101") (name "unconnected-(U$1-Pad9)") (class "Default")
      (node (ref "U$1") (pin "9") (pinfunction "9_9") (pintype "bidirectional"))
    )
    (net (code "102") (name "unconnected-(U$1-Pad22)") (class "Default")
      (node (ref "U$1") (pin "22") (pinfunction "22_22") (pintype "bidirectional"))
    )
    (net (code "103") (name "unconnected-(U$1-Pad23)") (class "Default")
      (node (ref "U$1") (pin "23") (pinfunction "23_23") (pintype "bidirectional"))
    )
    (net (code "104") (name "unconnected-(U$1-Pad24)") (class "Default")
      (node (ref "U$1") (pin "24") (pinfunction "24_24") (pintype "bidirectional"))
    )
    (net (code "105") (name "unconnected-(U$1-Pad25)") (class "Default")
      (node (ref "U$1") (pin "25") (pinfunction "25_25") (pintype "bidirectional"))
    )
    (net (code "106") (name "unconnected-(U$1-Pad26)") (class "Default")
      (node (ref "U$1") (pin "26") (pinfunction "26_26") (pintype "bidirectional"))
    )
    (net (code "107") (name "unconnected-(U$1-Pad27)") (class "Default")
      (node (ref "U$1") (pin "27") (pinfunction "27_27") (pintype "bidirectional"))
    )
    (net (code "108") (name "unconnected-(U$1-Pad28)") (class "Default")
      (node (ref "U$1") (pin "28") (pinfunction "28_28") (pintype "bidirectional"))
    )
    (net (code "109") (name "unconnected-(U$1-Pad29)") (class "Default")
      (node (ref "U$1") (pin "29") (pinfunction "29_29") (pintype "bidirectional"))
    )
    (net (code "110") (name "unconnected-(U$1-Pad30)") (class "Default")
      (node (ref "U$1") (pin "30") (pinfunction "30_30") (pintype "bidirectional"))
    )
    (net (code "111") (name "unconnected-(U$1-Pad31)") (class "Default")
      (node (ref "U$1") (pin "31") (pinfunction "31_31") (pintype "bidirectional"))
    )
    (net (code "112") (name "unconnected-(U$1-Pad33)") (class "Default")
      (node (ref "U$1") (pin "33") (pinfunction "33_33") (pintype "bidirectional"))
    )
    (net (code "113") (name "unconnected-(U$1-Pad34)") (class "Default")
      (node (ref "U$1") (pin "34") (pinfunction "34_34") (pintype "bidirectional"))
    )
    (net (code "114") (name "unconnected-(U$1-Pad35)") (class "Default")
      (node (ref "U$1") (pin "35") (pinfunction "35_35") (pintype "bidirectional"))
    )
    (net (code "115") (name "unconnected-(U$1-Pad36)") (class "Default")
      (node (ref "U$1") (pin "36") (pinfunction "36_36") (pintype "bidirectional"))
    )
    (net (code "116") (name "unconnected-(U$1-Pad37)") (class "Default")
      (node (ref "U$1") (pin "37") (pinfunction "37_37") (pintype "bidirectional"))
    )
    (net (code "117") (name "unconnected-(U$1-Pad38)") (class "Default")
      (node (ref "U$1") (pin "38") (pinfunction "38_38") (pintype "bidirectional"))
    )
    (net (code "118") (name "unconnected-(U$1-Pad39)") (class "Default")
      (node (ref "U$1") (pin "39") (pinfunction "39_39") (pintype "bidirectional"))
    )
    (net (code "119") (name "unconnected-(U$1-Pad40)") (class "Default")
      (node (ref "U$1") (pin "40") (pinfunction "40_40") (pintype "bidirectional"))
    )
    (net (code "120") (name "unconnected-(U$1-Pad41)") (class "Default")
      (node (ref "U$1") (pin "41") (pinfunction "41_41") (pintype "bidirectional"))
    )
    (net (code "121") (name "unconnected-(U$1-Pad42)") (class "Default")
      (node (ref "U$1") (pin "42") (pinfunction "42_42") (pintype "bidirectional"))
    )
    (net (code "122") (name "unconnected-(U$1-Pad43)") (class "Default")
      (node (ref "U$1") (pin "43") (pinfunction "43_43") (pintype "bidirectional"))
    )
    (net (code "123") (name "unconnected-(U$1-Pad44)") (class "Default")
      (node (ref "U$1") (pin "44") (pinfunction "44_44") (pintype "bidirectional"))
    )
    (net (code "124") (name "unconnected-(U$1-Pad45)") (class "Default")
      (node (ref "U$1") (pin "45") (pinfunction "45_45") (pintype "bidirectional"))
    )
    (net (code "125") (name "unconnected-(U$1-Pad46)") (class "Default")
      (node (ref "U$1") (pin "46") (pinfunction "46_46") (pintype "bidirectional"))
    )
    (net (code "126") (name "unconnected-(U$1-Pad47)") (class "Default")
      (node (ref "U$1") (pin "47") (pinfunction "47_47") (pintype "bidirectional"))
    )
    (net (code "127") (name "unconnected-(U$1-Pad48)") (class "Default")
      (node (ref "U$1") (pin "48") (pinfunction "48_48") (pintype "bidirectional"))
    )
    (net (code "128") (name "unconnected-(U$1-Pad49)") (class "Default")
      (node (ref "U$1") (pin "49") (pinfunction "49_49") (pintype "bidirectional"))
    )
    (net (code "129") (name "unconnected-(U$1-Pad50)") (class "Default")
      (node (ref "U$1") (pin "50") (pinfunction "50_50") (pintype "bidirectional"))
    )
    (net (code "130") (name "unconnected-(U$1-Pad51)") (class "Default")
      (node (ref "U$1") (pin "51") (pinfunction "51_51") (pintype "bidirectional"))
    )
    (net (code "131") (name "unconnected-(U$1-PadA1)") (class "Default")
      (node (ref "U$1") (pin "A1") (pinfunction "A1_A1") (pintype "bidirectional"))
    )
    (net (code "132") (name "unconnected-(U$1-PadA2)") (class "Default")
      (node (ref "U$1") (pin "A2") (pinfunction "A2_A2") (pintype "bidirectional"))
    )
    (net (code "133") (name "unconnected-(U$1-PadA6)") (class "Default")
      (node (ref "U$1") (pin "A6") (pinfunction "A6_A6") (pintype "bidirectional"))
    )
    (net (code "134") (name "unconnected-(U$1-PadA7)") (class "Default")
      (node (ref "U$1") (pin "A7") (pinfunction "A7_A7") (pintype "bidirectional"))
    )
    (net (code "135") (name "unconnected-(U$1-PadA8)") (class "Default")
      (node (ref "U$1") (pin "A8") (pinfunction "A8_A8") (pintype "bidirectional"))
    )
    (net (code "136") (name "unconnected-(U$1-PadA9)") (class "Default")
      (node (ref "U$1") (pin "A9") (pinfunction "A9_A9") (pintype "bidirectional"))
    )
    (net (code "137") (name "unconnected-(U$1-PadA10)") (class "Default")
      (node (ref "U$1") (pin "A10") (pinfunction "A10_A10") (pintype "bidirectional"))
    )
    (net (code "138") (name "unconnected-(U$1-PadA11)") (class "Default")
      (node (ref "U$1") (pin "A11") (pinfunction "A11_A11") (pintype "bidirectional"))
    )
    (net (code "139") (name "unconnected-(U$1-PadAREF)") (class "Default")
      (node (ref "U$1") (pin "AREF") (pinfunction "AREF_AREF") (pintype "bidirectional"))
    )
    (net (code "140") (name "unconnected-(U$1-PadRESET.)") (class "Default")
      (node (ref "U$1") (pin "RESET.") (pinfunction "RESET._RESET.") (pintype "bidirectional"))
    )
    (net (code "141") (name "unconnected-(U$5-AD0-Pad38)") (class "Default")
      (node (ref "U$5") (pin "38") (pinfunction "AD0_38") (pintype "bidirectional"))
    )
    (net (code "142") (name "unconnected-(U$5-AD1-Pad39)") (class "Default")
      (node (ref "U$5") (pin "39") (pinfunction "AD1_39") (pintype "bidirectional"))
    )
    (net (code "143") (name "unconnected-(U$5-AD2-Pad40)") (class "Default")
      (node (ref "U$5") (pin "40") (pinfunction "AD2_40") (pintype "bidirectional"))
    )
    (net (code "144") (name "unconnected-(U$5-AD3-Pad41)") (class "Default")
      (node (ref "U$5") (pin "41") (pinfunction "AD3_41") (pintype "bidirectional"))
    )
    (net (code "145") (name "unconnected-(U$5-AD4-Pad5)") (class "Default")
      (node (ref "U$5") (pin "5") (pinfunction "AD4_5") (pintype "bidirectional"))
    )
    (net (code "146") (name "unconnected-(U$5-AD5-Pad6)") (class "Default")
      (node (ref "U$5") (pin "6") (pinfunction "AD5_6") (pintype "bidirectional"))
    )
    (net (code "147") (name "unconnected-(U$5-AD6-Pad7)") (class "Default")
      (node (ref "U$5") (pin "7") (pinfunction "AD6_7") (pintype "bidirectional"))
    )
    (net (code "148") (name "unconnected-(U$5-AD7-Pad8)") (class "Default")
      (node (ref "U$5") (pin "8") (pinfunction "AD7_8") (pintype "bidirectional"))
    )
    (net (code "149") (name "unconnected-(U$5-AD8-Pad25)") (class "Default")
      (node (ref "U$5") (pin "25") (pinfunction "AD8_25") (pintype "bidirectional"))
    )
    (net (code "150") (name "unconnected-(U$5-AD9-Pad26)") (class "Default")
      (node (ref "U$5") (pin "26") (pinfunction "AD9_26") (pintype "bidirectional"))
    )
    (net (code "151") (name "unconnected-(U$5-AD10-Pad27)") (class "Default")
      (node (ref "U$5") (pin "27") (pinfunction "AD10_27") (pintype "bidirectional"))
    )
    (net (code "152") (name "unconnected-(U$5-AD11-Pad28)") (class "Default")
      (node (ref "U$5") (pin "28") (pinfunction "AD11_28") (pintype "bidirectional"))
    )
    (net (code "153") (name "unconnected-(U$5-AD12-Pad29)") (class "Default")
      (node (ref "U$5") (pin "29") (pinfunction "AD12_29") (pintype "bidirectional"))
    )
    (net (code "154") (name "unconnected-(U$5-AD13-Pad30)") (class "Default")
      (node (ref "U$5") (pin "30") (pinfunction "AD13_30") (pintype "bidirectional"))
    )
    (net (code "155") (name "unconnected-(U$5-AD14-Pad31)") (class "Default")
      (node (ref "U$5") (pin "31") (pinfunction "AD14_31") (pintype "bidirectional"))
    )
    (net (code "156") (name "unconnected-(U$5-CLKOUT-Pad23)") (class "Default")
      (node (ref "U$5") (pin "23") (pinfunction "CLKOUT_23") (pintype "output"))
    )
    (net (code "157") (name "unconnected-(U$5-OSC2-Pad2)") (class "Default")
      (node (ref "U$5") (pin "2") (pinfunction "OSC2_2") (pintype "output"))
    )
    (net (code "158") (name "unconnected-(U$5-PSPCFG0-Pad32)") (class "Default")
      (node (ref "U$5") (pin "32") (pinfunction "PSPCFG0_32") (pintype "output"))
    )
    (net (code "159") (name "unconnected-(XB1-AD0{slash}DIO0-Pad20)") (class "Default")
      (node (ref "XB1") (pin "20") (pinfunction "AD0/DIO0_20") (pintype "bidirectional"))
    )
    (net (code "160") (name "unconnected-(XB1-AD1{slash}DIO1-Pad19)") (class "Default")
      (node (ref "XB1") (pin "19") (pinfunction "AD1/DIO1_19") (pintype "bidirectional"))
    )
    (net (code "161") (name "unconnected-(XB1-AD2{slash}DIO2-Pad18)") (class "Default")
      (node (ref "XB1") (pin "18") (pinfunction "AD2/DIO2_18") (pintype "bidirectional"))
    )
    (net (code "162") (name "unconnected-(XB1-ASSOC{slash}AD5{slash}DIO5-Pad15)") (class "Default")
      (node (ref "XB1") (pin "15") (pinfunction "ASSOC/AD5/DIO5_15") (pintype "bidirectional"))
    )
    (net (code "163") (name "unconnected-(XB1-CD{slash}DOUT_EN{slash}DO8-Pad4)") (class "Default")
      (node (ref "XB1") (pin "4") (pinfunction "CD/DOUT_EN/DO8_4") (pintype "output"))
    )
    (net (code "164") (name "unconnected-(XB1-COORD_SEL{slash}AD3{slash}DIO3-Pad17)") (class "Default")
      (node (ref "XB1") (pin "17") (pinfunction "COORD_SEL/AD3/DIO3_17") (pintype "bidirectional"))
    )
    (net (code "165") (name "unconnected-(XB1-ON{slash}~{SLEEP}-Pad13)") (class "Default")
      (node (ref "XB1") (pin "13") (pinfunction "ON/~{SLEEP}_13") (pintype "output"))
    )
    (net (code "166") (name "unconnected-(XB1-PWM0{slash}RSSI-Pad6)") (class "Default")
      (node (ref "XB1") (pin "6") (pinfunction "PWM0/RSSI_6") (pintype "output"))
    )
    (net (code "167") (name "unconnected-(XB1-RF_TX{slash}AD4{slash}DIO4-Pad11)") (class "Default")
      (node (ref "XB1") (pin "11") (pinfunction "RF_TX/AD4/DIO4_11") (pintype "bidirectional"))
    )
    (net (code "168") (name "unconnected-(XB1-VREF-Pad14)") (class "Default")
      (node (ref "XB1") (pin "14") (pinfunction "VREF_14") (pintype "input"))
    )
  )
)
